# robot.net
KiCad netlist of a schematic drawn in EAGLE
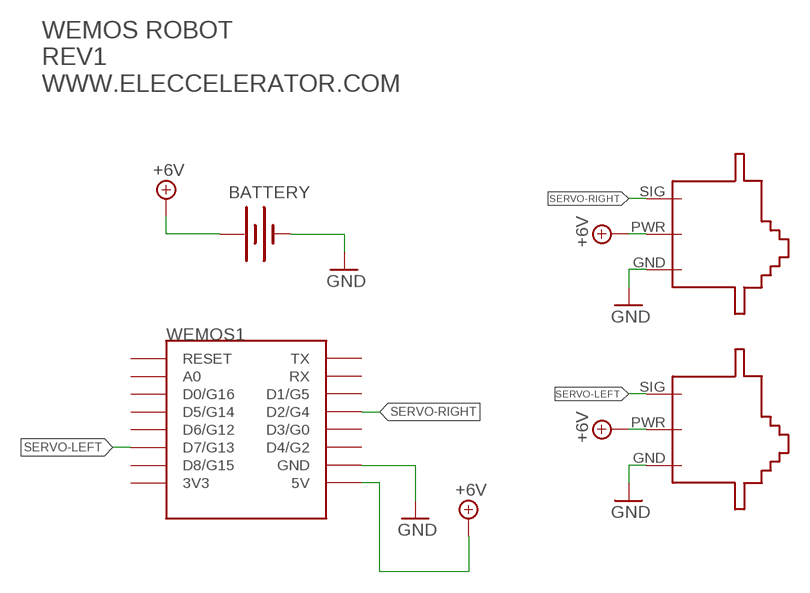
[diagram p0: schematic, sheet 1]

(export (version "E")
  (design (tool "Eeschema 10.0.6"))
  (components
    (comp (ref "BATTERY")
      (value "BATTERY-WIRE-CONN")
      (footprint "eagle-import:BATT-WIRE-CONN")
      (libsource (lib "eagle-import") (part "BATTERY-WIRE-CONN"))
    )
    (comp (ref "M1")
      (value "SERVO-FLIPPED")
      (footprint "eagle-import:SERVO-FLIPPED")
      (libsource (lib "eagle-import") (part "SERVO-FLIPPED"))
    )
    (comp (ref "M2")
      (value "SERVO-1")
      (footprint "eagle-import:SERVO")
      (libsource (lib "eagle-import") (part "SERVO-1"))
    )
    (comp (ref "U$1")
      (value "HACKADAY-14MM")
      (footprint "eagle-import:HACKADAY-1")
      (libsource (lib "eagle-import") (part "HACKADAY-14MM"))
    )
    (comp (ref "U$9")
      (value "TEXT-INFO-MINI")
      (footprint "eagle-import:TEXT-INFO-MINI")
      (libsource (lib "eagle-import") (part "TEXT-INFO-MINI"))
    )
    (comp (ref "WEMOS1")
      (value "WEMOS-D1-MINI")
      (footprint "eagle-import:WEMOS-D1-MINI")
      (libsource (lib "eagle-import") (part "WEMOS-D1-MINI"))
    )
  )
  (nets
    (net (code "1") (name "+6V") (class "Default")
      (node (ref "BATTERY") (pin "POS") (pinfunction "+_POS") (pintype "power_in"))
      (node (ref "M1") (pin "PWR") (pinfunction "PWR_PWR") (pintype "bidirectional"))
      (node (ref "M2") (pin "PWR") (pinfunction "PWR_PWR") (pintype "bidirectional"))
      (node (ref "WEMOS1") (pin "5V") (pinfunction "5V_5V") (pintype "bidirectional"))
    )
    (net (code "2") (name "GND") (class "Default")
      (node (ref "BATTERY") (pin "NEG") (pinfunction "-_NEG") (pintype "power_in"))
      (node (ref "M1") (pin "GND") (pinfunction "GND_GND") (pintype "bidirectional"))
      (node (ref "M2") (pin "GND") (pinfunction "GND_GND") (pintype "bidirectional"))
      (node (ref "WEMOS1") (pin "GND") (pinfunction "GND_GND") (pintype "bidirectional"))
    )
    (net (code "3") (name "SERVO-LEFT") (class "Default")
      (node (ref "M1") (pin "SIG") (pinfunction "SIG_SIG") (pintype "bidirectional"))
      (node (ref "WEMOS1") (pin "D7") (pinfunction "D7/G13_D7") (pintype "bidirectional"))
    )
    (net (code "4") (name "SERVO-RIGHT") (class "Default")
      (node (ref "M2") (pin "SIG") (pinfunction "SIG_SIG") (pintype "bidirectional"))
      (node (ref "WEMOS1") (pin "D2") (pinfunction "D2/G4_D2") (pintype "bidirectional"))
    )
    (net (code "5") (name "unconnected-(WEMOS1-D0{slash}G16-PadD0)") (class "Default")
      (node (ref "WEMOS1") (pin "D0") (pinfunction "D0/G16_D0") (pintype "bidirectional"))
    )
    (net (code "6") (name "unconnected-(WEMOS1-D1{slash}G5-PadD1)") (class "Default")
      (node (ref "WEMOS1") (pin "D1") (pinfunction "D1/G5_D1") (pintype "bidirectional"))
    )
    (net (code "7") (name "unconnected-(WEMOS1-D3{slash}G0-PadD3)") (class "Default")
      (node (ref "WEMOS1") (pin "D3") (pinfunction "D3/G0_D3") (pintype "bidirectional"))
    )
    (net (code "8") (name "unconnected-(WEMOS1-D4{slash}G2-PadD4)") (class "Default")
      (node (ref "WEMOS1") (pin "D4") (pinfunction "D4/G2_D4") (pintype "bidirectional"))
    )
    (net (code "9") (name "unconnected-(WEMOS1-D5{slash}G14-PadD5)") (class "Default")
      (node (ref "WEMOS1") (pin "D5") (pinfunction "D5/G14_D5") (pintype "bidirectional"))
    )
    (net (code "10") (name "unconnected-(WEMOS1-D6{slash}G12-PadD6)") (class "Default")
      (node (ref "WEMOS1") (pin "D6") (pinfunction "D6/G12_D6") (pintype "bidirectional"))
    )
    (net (code "11") (name "unconnected-(WEMOS1-D8{slash}G15-PadD8)") (class "Default")
      (node (ref "WEMOS1") (pin "D8") (pinfunction "D8/G15_D8") (pintype "bidirectional"))
    )
    (net (code "12") (name "unconnected-(WEMOS1-Pad3V3)") (class "Default")
      (node (ref "WEMOS1") (pin "3V3") (pinfunction "3V3_3V3") (pintype "bidirectional"))
    )
    (net (code "13") (name "unconnected-(WEMOS1-PadA0)") (class "Default")
      (node (ref "WEMOS1") (pin "A0") (pinfunction "A0_A0") (pintype "bidirectional"))
    )
    (net (code "14") (name "unconnected-(WEMOS1-PadRESET)") (class "Default")
      (node (ref "WEMOS1") (pin "RESET") (pinfunction "RESET_RESET") (pintype "bidirectional"))
    )
    (net (code "15") (name "unconnected-(WEMOS1-PadRX)") (class "Default")
      (node (ref "WEMOS1") (pin "RX") (pinfunction "RX_RX") (pintype "bidirectional"))
    )
    (net (code "16") (name "unconnected-(WEMOS1-PadTX)") (class "Default")
      (node (ref "WEMOS1") (pin "TX") (pinfunction "TX_TX") (pintype "bidirectional"))
    )
  )
)
